# F407.net
KiCad netlist of a schematic drawn in Altium Designer
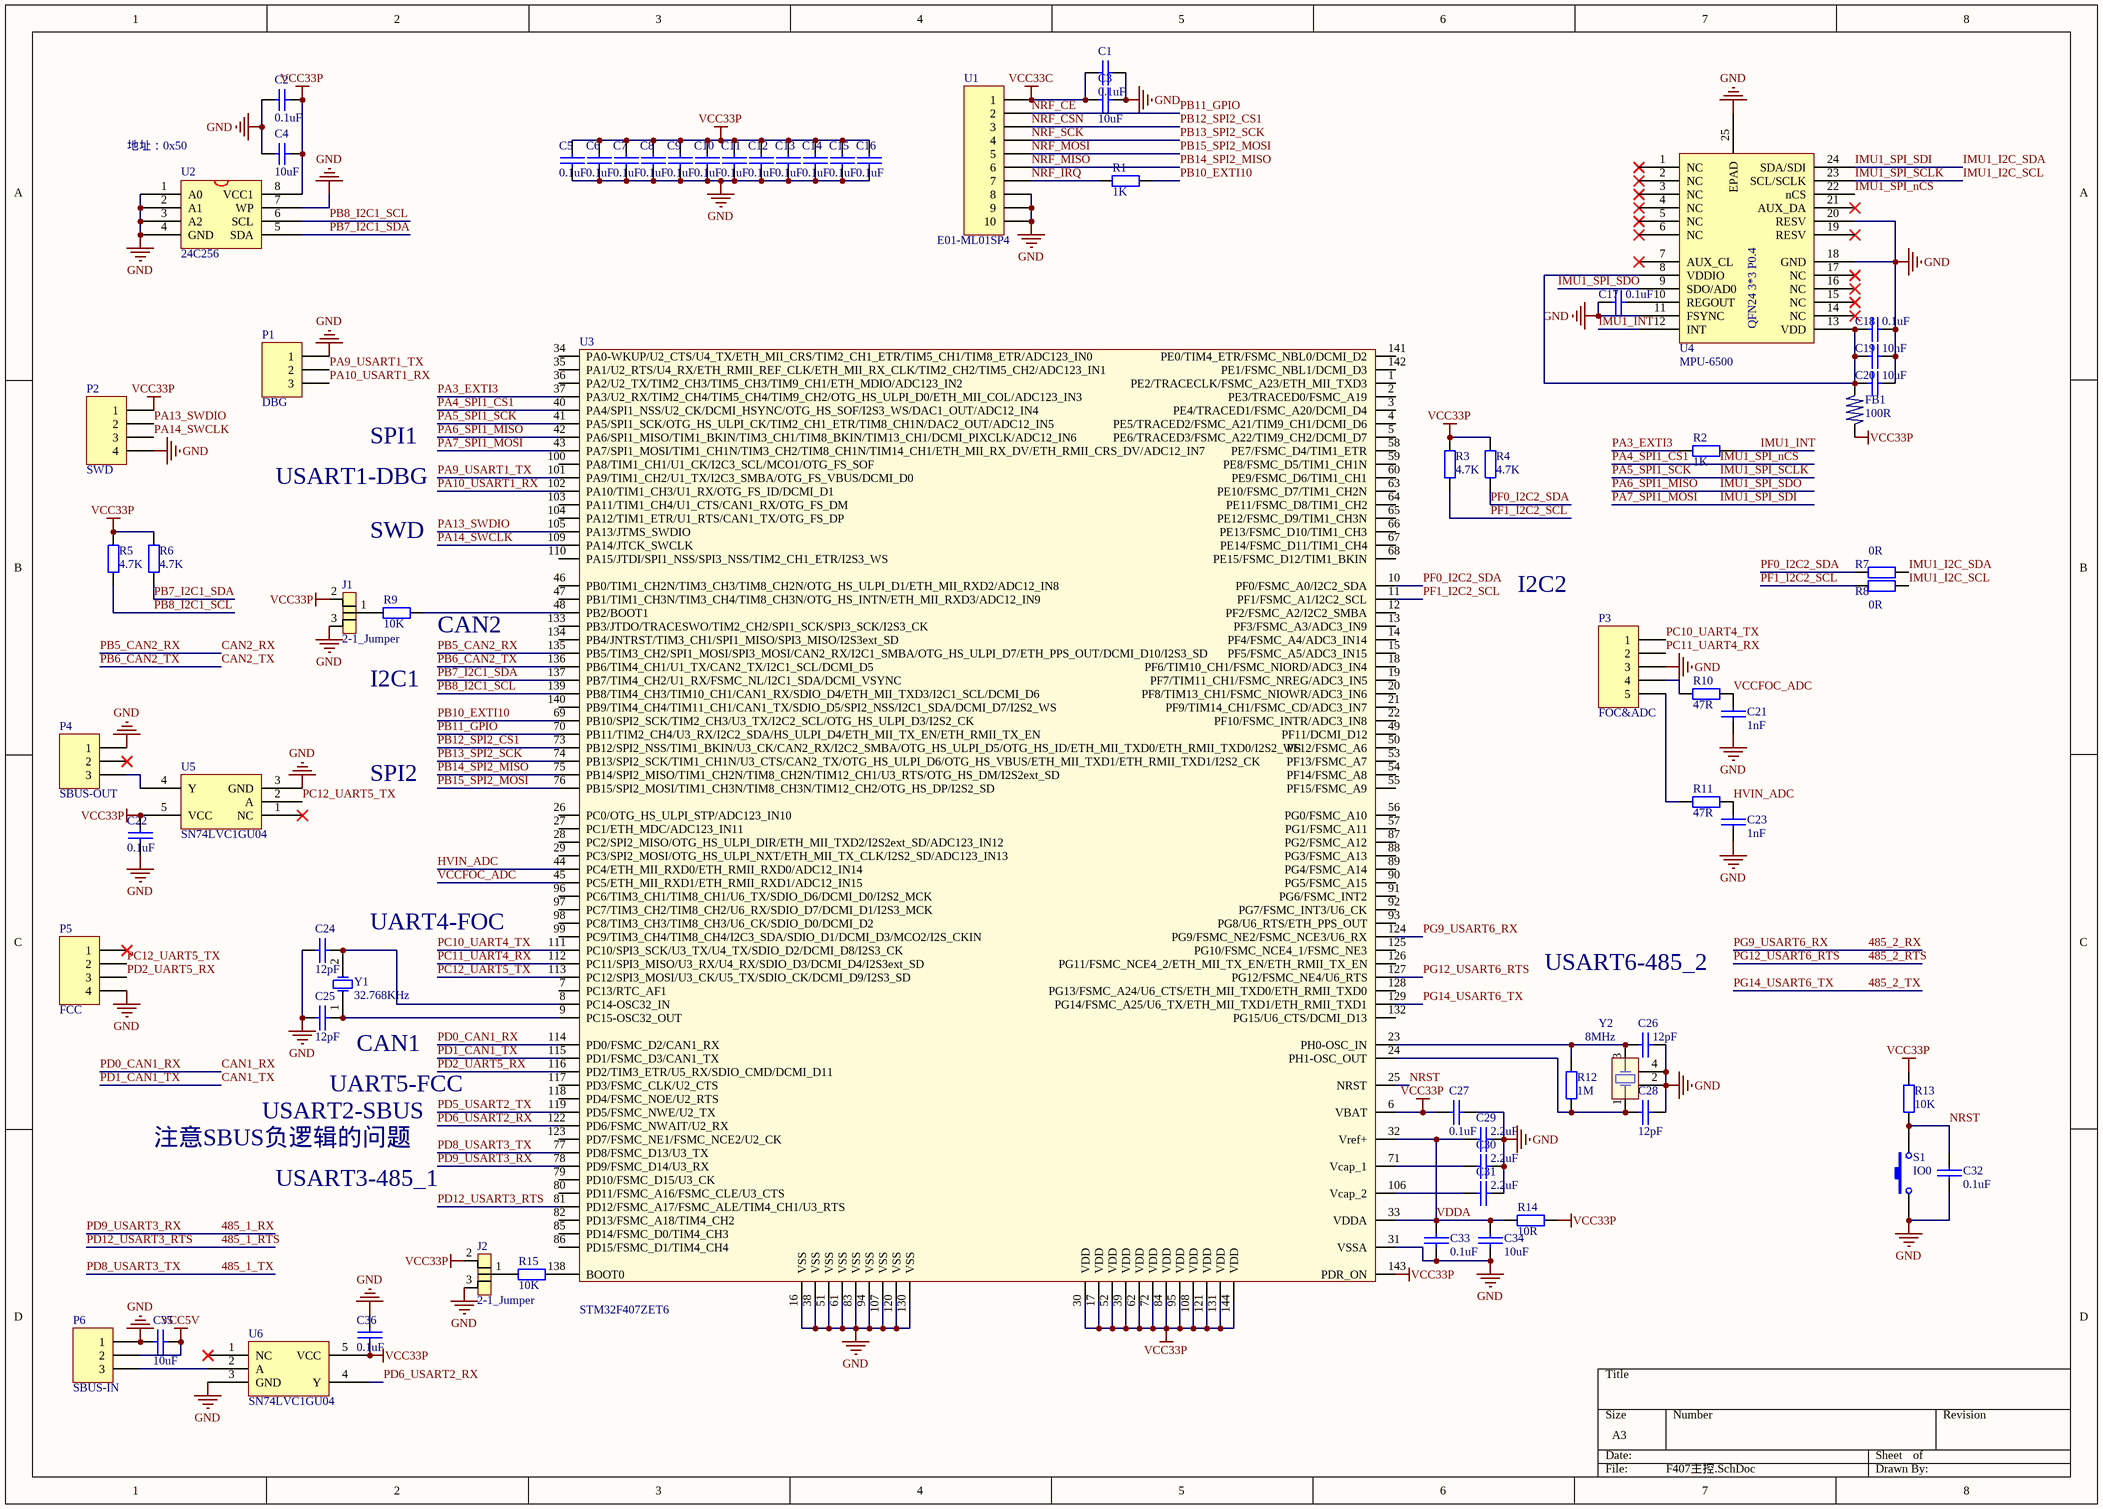
[diagram p0: F407主控.SchDoc]

(export (version "E")
  (design (tool "Eeschema 10.0.6"))
  (components
    (comp (ref "C1")
      (value "0.1uF")
      (footprint "C0805_M")
      (description "Capacitor")
      (libsource (lib "*") (part "CAP"))
    )
    (comp (ref "C2")
      (value "0.1uF")
      (footprint "C0805_M")
      (description "Capacitor")
      (fields (field (name "PUBLISHER") "Altium Limited"))
      (libsource (lib "Miscellaneous Devices") (part "Cap"))
    )
    (comp (ref "C3")
      (value "10uF")
      (footprint "C0805_M")
      (description "Capacitor")
      (libsource (lib "*") (part "CAP"))
    )
    (comp (ref "C4")
      (value "10uF")
      (footprint "C0805_M")
      (description "Capacitor")
      (fields (field (name "PUBLISHER") "Altium Limited"))
      (libsource (lib "Miscellaneous Devices") (part "Cap"))
    )
    (comp (ref "C5")
      (value "0.1uF")
      (footprint "C0805_M")
      (description "Capacitor")
      (libsource (lib "*") (part "CAP"))
    )
    (comp (ref "C6")
      (value "0.1uF")
      (footprint "C0805_M")
      (description "Capacitor")
      (libsource (lib "*") (part "CAP"))
    )
    (comp (ref "C7")
      (value "0.1uF")
      (footprint "C0805_M")
      (description "Capacitor")
      (libsource (lib "*") (part "CAP"))
    )
    (comp (ref "C8")
      (value "0.1uF")
      (footprint "C0805_M")
      (description "Capacitor")
      (libsource (lib "*") (part "CAP"))
    )
    (comp (ref "C9")
      (value "0.1uF")
      (footprint "C0805_M")
      (description "Capacitor")
      (libsource (lib "*") (part "CAP"))
    )
    (comp (ref "C10")
      (value "0.1uF")
      (footprint "C0805_M")
      (description "Capacitor")
      (libsource (lib "*") (part "CAP"))
    )
    (comp (ref "C11")
      (value "0.1uF")
      (footprint "C0805_M")
      (description "Capacitor")
      (libsource (lib "*") (part "CAP"))
    )
    (comp (ref "C12")
      (value "0.1uF")
      (footprint "C0805_M")
      (description "Capacitor")
      (libsource (lib "*") (part "CAP"))
    )
    (comp (ref "C13")
      (value "0.1uF")
      (footprint "C0805_M")
      (description "Capacitor")
      (libsource (lib "*") (part "CAP"))
    )
    (comp (ref "C14")
      (value "0.1uF")
      (footprint "C0805_M")
      (description "Capacitor")
      (libsource (lib "*") (part "CAP"))
    )
    (comp (ref "C15")
      (value "0.1uF")
      (footprint "C0805_M")
      (description "Capacitor")
      (libsource (lib "*") (part "CAP"))
    )
    (comp (ref "C16")
      (value "0.1uF")
      (footprint "C0805_M")
      (description "Capacitor")
      (libsource (lib "*") (part "CAP"))
    )
    (comp (ref "C17")
      (value "0.1uF")
      (footprint "C0805_M")
      (description "Capacitor")
      (libsource (lib "*") (part "CAP"))
    )
    (comp (ref "C18")
      (value "0.1uF")
      (footprint "C0805_M")
      (description "Capacitor")
      (libsource (lib "*") (part "CAP"))
    )
    (comp (ref "C19")
      (value "10nF")
      (footprint "C0805_M")
      (description "Capacitor")
      (libsource (lib "*") (part "CAP"))
    )
    (comp (ref "C20")
      (value "10uF")
      (footprint "C0805_M")
      (description "Capacitor")
      (libsource (lib "*") (part "CAP"))
    )
    (comp (ref "C21")
      (value "1nF")
      (footprint "C0805_M")
      (description "Capacitor")
      (libsource (lib "*") (part "CAP"))
    )
    (comp (ref "C22")
      (value "0.1uF")
      (footprint "C0805_M")
      (description "Capacitor")
      (libsource (lib "*") (part "CAP"))
    )
    (comp (ref "C23")
      (value "1nF")
      (footprint "C0805_M")
      (description "Capacitor")
      (libsource (lib "*") (part "CAP"))
    )
    (comp (ref "C24")
      (value "12pF")
      (footprint "C0805_M")
      (description "Capacitor")
      (libsource (lib "*") (part "CAP"))
    )
    (comp (ref "C25")
      (value "12pF")
      (footprint "C0805_M")
      (description "Capacitor")
      (libsource (lib "*") (part "CAP"))
    )
    (comp (ref "C26")
      (value "12pF")
      (footprint "C0805_M")
      (description "Capacitor")
      (libsource (lib "*") (part "CAP"))
    )
    (comp (ref "C27")
      (value "0.1uF")
      (footprint "C0805_M")
      (description "Capacitor")
      (libsource (lib "*") (part "CAP"))
    )
    (comp (ref "C28")
      (value "12pF")
      (footprint "C0805_M")
      (description "Capacitor")
      (libsource (lib "*") (part "CAP"))
    )
    (comp (ref "C29")
      (value "2.2uF")
      (footprint "C0805_M")
      (description "Capacitor")
      (libsource (lib "*") (part "CAP"))
    )
    (comp (ref "C30")
      (value "2.2uF")
      (footprint "C0805_M")
      (description "Capacitor")
      (libsource (lib "*") (part "CAP"))
    )
    (comp (ref "C31")
      (value "2.2uF")
      (footprint "C0805_M")
      (description "Capacitor")
      (libsource (lib "*") (part "CAP"))
    )
    (comp (ref "C32")
      (value "0.1uF")
      (footprint "C0805_M")
      (description "Capacitor")
      (libsource (lib "*") (part "CAP"))
    )
    (comp (ref "C33")
      (value "0.1uF")
      (footprint "C0805_M")
      (description "Capacitor")
      (libsource (lib "*") (part "CAP"))
    )
    (comp (ref "C34")
      (value "10uF")
      (footprint "C0805_M")
      (description "Capacitor")
      (libsource (lib "*") (part "CAP"))
    )
    (comp (ref "C35")
      (value "10uF")
      (footprint "C0805_M")
      (description "Capacitor")
      (libsource (lib "*") (part "CAP"))
    )
    (comp (ref "C36")
      (value "0.1uF")
      (footprint "C0805_M")
      (description "Capacitor")
      (libsource (lib "*") (part "CAP"))
    )
    (comp (ref "FB1") (value "100R") (footprint "R0805_M") (libsource (lib "EXPLORER") (part "L")))
    (comp (ref "J1")
      (value "2-1_Jumper")
      (footprint "2-1_Jumper")
      (libsource (lib "XL6005") (part "2-1_Jumper"))
    )
    (comp (ref "J2")
      (value "2-1_Jumper")
      (footprint "2-1_Jumper")
      (libsource (lib "XL6005") (part "2-1_Jumper"))
    )
    (comp (ref "P1")
      (value "DBG")
      (footprint "XH2.54-LI-3P")
      (description "Header, 3-Pin")
      (fields (field (name "PUBLISHER") "Altium Limited"))
      (libsource (lib "Miscellaneous Connectors") (part "Header 3"))
    )
    (comp (ref "P2")
      (value "SWD")
      (footprint "XH2.54-LI-4P")
      (description "Header, 4-Pin")
      (fields (field (name "PUBLISHER") "Altium Limited"))
      (libsource (lib "Miscellaneous Connectors") (part "Header 4"))
    )
    (comp (ref "P3")
      (value "FOC&ADC")
      (footprint "XH2.54-LI-5P")
      (description "Header, 5-Pin")
      (fields (field (name "PUBLISHER") "Altium Limited"))
      (libsource (lib "Miscellaneous Connectors") (part "Header 5"))
    )
    (comp (ref "P4")
      (value "SBUS-OUT")
      (footprint "XH2.54-LI-3P")
      (description "Header, 3-Pin")
      (fields (field (name "PUBLISHER") "Altium Limited"))
      (libsource (lib "Miscellaneous Connectors") (part "Header 3"))
    )
    (comp (ref "P5")
      (value "FCC")
      (footprint "XH2.54-LI-4P")
      (description "Header, 4-Pin")
      (fields (field (name "PUBLISHER") "Altium Limited"))
      (libsource (lib "Miscellaneous Connectors") (part "Header 4"))
    )
    (comp (ref "P6")
      (value "SBUS-IN")
      (footprint "XH2.54-LI-3P")
      (description "Header, 3-Pin")
      (fields (field (name "PUBLISHER") "Altium Limited"))
      (libsource (lib "Miscellaneous Connectors") (part "Header 3"))
    )
    (comp (ref "R1")
      (value "1K")
      (footprint "R0805_M")
      (description "Resistor")
      (fields (field (name "PUBLISHER") "Altium Limited"))
      (libsource (lib "") (part "Res2_1"))
    )
    (comp (ref "R2")
      (value "1K")
      (footprint "R0805_M")
      (description "Resistor")
      (fields (field (name "PUBLISHER") "Altium Limited"))
      (libsource (lib "") (part "Res2_1"))
    )
    (comp (ref "R3")
      (value "4.7K")
      (footprint "R0805_M")
      (description "Resistor")
      (fields (field (name "PUBLISHER") "Altium Limited"))
      (libsource (lib "") (part "Res2_2"))
    )
    (comp (ref "R4")
      (value "4.7K")
      (footprint "R0805_M")
      (description "Resistor")
      (fields (field (name "PUBLISHER") "Altium Limited"))
      (libsource (lib "") (part "Res2_2"))
    )
    (comp (ref "R5")
      (value "4.7K")
      (footprint "R0805_M")
      (description "Resistor")
      (fields (field (name "PUBLISHER") "Altium Limited"))
      (libsource (lib "") (part "Res2_2"))
    )
    (comp (ref "R6")
      (value "4.7K")
      (footprint "R0805_M")
      (description "Resistor")
      (fields (field (name "PUBLISHER") "Altium Limited"))
      (libsource (lib "") (part "Res2_2"))
    )
    (comp (ref "R7")
      (value "0R")
      (footprint "R0805_M")
      (description "Resistor")
      (fields (field (name "PUBLISHER") "Altium Limited"))
      (libsource (lib "") (part "Res2_1"))
    )
    (comp (ref "R8")
      (value "0R")
      (footprint "R0805_M")
      (description "Resistor")
      (fields (field (name "PUBLISHER") "Altium Limited"))
      (libsource (lib "") (part "Res2_1"))
    )
    (comp (ref "R9")
      (value "10K")
      (footprint "R0805_M")
      (description "Resistor")
      (fields (field (name "PUBLISHER") "Altium Limited"))
      (libsource (lib "") (part "Res2_1"))
    )
    (comp (ref "R10")
      (value "47R")
      (footprint "R0805_M")
      (description "Resistor")
      (fields (field (name "PUBLISHER") "Altium Limited"))
      (libsource (lib "Miscellaneous Devices") (part "Res2"))
    )
    (comp (ref "R11")
      (value "47R")
      (footprint "R0805_M")
      (description "Resistor")
      (fields (field (name "PUBLISHER") "Altium Limited"))
      (libsource (lib "Miscellaneous Devices") (part "Res2"))
    )
    (comp (ref "R12")
      (value "1M")
      (footprint "R0805_M")
      (description "Resistor")
      (fields (field (name "PUBLISHER") "Altium Limited"))
      (libsource (lib "") (part "Res2_3"))
    )
    (comp (ref "R13")
      (value "10K")
      (footprint "R0805_M")
      (description "Resistor")
      (fields (field (name "PUBLISHER") "Altium Limited"))
      (libsource (lib "") (part "Res2_2"))
    )
    (comp (ref "R14")
      (value "10R")
      (footprint "R0805_M")
      (description "Resistor")
      (fields (field (name "PUBLISHER") "Altium Limited"))
      (libsource (lib "") (part "Res2_1"))
    )
    (comp (ref "R15")
      (value "10K")
      (footprint "R0805_M")
      (description "Resistor")
      (fields (field (name "PUBLISHER") "Altium Limited"))
      (libsource (lib "") (part "Res2_1"))
    )
    (comp (ref "S1")
      (value "IO0")
      (footprint "KEY_M")
      (description "Switch")
      (fields (field (name "PUBLISHER") "Altium Limited"))
      (libsource (lib "Miscellaneous Devices") (part "SW-PB"))
    )
    (comp (ref "U1")
      (value "E01-ML01SP4")
      (footprint "PE01-ML01SP4")
      (description "Header, 10-Pin")
      (fields (field (name "PUBLISHER") "Altium Limited"))
      (libsource (lib "Miscellaneous Connectors") (part "Header 10"))
    )
    (comp (ref "U2")
      (value "24C256")
      (footprint "SOP-8")
      (libsource (lib "Explorer STM32F407封装库") (part "24C256"))
    )
    (comp (ref "U3")
      (value "STM32F407ZET6")
      (footprint "2.12-矩形QFP封装:LQFP144")
      (libsource (lib "EXPLORER") (part "STM32F407ZET6"))
    )
    (comp (ref "U4")
      (value "MPU-6500")
      (footprint "QFN24-L3.0-W3.0-P0.4")
      (description "6 DoF IMU Footprint QFN24 3*3 P0.4")
      (libsource (lib "XL6005") (part "MPU-6500"))
    )
    (comp (ref "U5")
      (value "SN74LVC1GU04")
      (footprint "SOT-23-5")
      (libsource (lib "") (part "SN74LVC1GU04_1"))
    )
    (comp (ref "U6")
      (value "SN74LVC1GU04")
      (footprint "SOT-23-5")
      (libsource (lib "7688A原理图封装") (part "SN74LVC1GU04"))
    )
    (comp (ref "Y1")
      (value "32.768KHz")
      (footprint "OSC-3215-2P")
      (description "CL=12.5pF")
      (fields (field (name "PUBLISHER") "Altium Limited"))
      (libsource (lib "Miscellaneous Devices") (part "XTAL"))
    )
    (comp (ref "Y2")
      (value "8MHz")
      (footprint "1.09-晶振、晶体:OSC-3225-4P")
      (description "CL=12pF")
      (fields (field (name "PUBLISHER") "Altium Limited"))
      (libsource (lib "XL6005") (part "XTAL-4"))
    )
  )
  (nets
    (net (code "1") (name "/485_1_RTS") (class "Default")
      (node (ref "U3") (pin "81") (pinfunction "PD12/FSMC_A17/FSMC_ALE/TIM4_CH1/U3_RTS_81") (pintype "passive"))
    )
    (net (code "2") (name "/485_1_RX") (class "Default")
      (node (ref "U3") (pin "78") (pinfunction "PD9/FSMC_D14/U3_RX_78") (pintype "passive"))
    )
    (net (code "3") (name "/485_1_TX") (class "Default")
      (node (ref "U3") (pin "77") (pinfunction "PD8/FSMC_D13/U3_TX_77") (pintype "passive"))
    )
    (net (code "4") (name "/485_2_RTS") (class "Default")
      (node (ref "U3") (pin "127") (pinfunction "PG12/FSMC_NE4/U6_RTS_127") (pintype "passive"))
    )
    (net (code "5") (name "/485_2_RX") (class "Default")
      (node (ref "U3") (pin "124") (pinfunction "PG9/FSMC_NE2/FSMC_NCE3/U6_RX_124") (pintype "passive"))
    )
    (net (code "6") (name "/485_2_TX") (class "Default")
      (node (ref "U3") (pin "129") (pinfunction "PG14/FSMC_A25/U6_TX/ETH_MII_TXD1/ETH_RMII_TXD1_129") (pintype "passive"))
    )
    (net (code "7") (name "/CAN1_RX") (class "Default")
      (node (ref "U3") (pin "114") (pinfunction "PD0/FSMC_D2/CAN1_RX_114") (pintype "passive"))
    )
    (net (code "8") (name "/CAN1_TX") (class "Default")
      (node (ref "U3") (pin "115") (pinfunction "PD1/FSMC_D3/CAN1_TX_115") (pintype "passive"))
    )
    (net (code "9") (name "/CAN2_RX") (class "Default")
      (node (ref "U3") (pin "135") (pinfunction "PB5/TIM3_CH2/SPI1_MOSI/SPI3_MOSI/CAN2_RX/I2C1_SMBA/OTG_HS_ULPI_D7/ETH_PPS_OUT/DCMI_D10/I2S3_SD_135") (pintype "passive"))
    )
    (net (code "10") (name "/CAN2_TX") (class "Default")
      (node (ref "U3") (pin "136") (pinfunction "PB6/TIM4_CH1/U1_TX/CAN2_TX/I2C1_SCL/DCMI_D5_136") (pintype "passive"))
    )
    (net (code "11") (name "/HVIN_ADC") (class "Default")
      (node (ref "C23") (pin "2") (pinfunction "2_2") (pintype "passive"))
      (node (ref "R11") (pin "2") (pinfunction "2_2") (pintype "passive"))
      (node (ref "U3") (pin "44") (pinfunction "PC4/ETH_MII_RXD0/ETH_RMII_RXD0/ADC12_IN14_44") (pintype "passive"))
    )
    (net (code "12") (name "/IMU1_I2C_SCL") (class "Default")
      (node (ref "R8") (pin "1") (pinfunction "1_1") (pintype "passive"))
      (node (ref "U3") (pin "41") (pinfunction "PA5/SPI1_SCK/OTG_HS_ULPI_CK/TIM2_CH1_ETR/TIM8_CH1N/DAC2_OUT/ADC12_IN5_41") (pintype "passive"))
      (node (ref "U4") (pin "23") (pinfunction "SCL/SCLK_23") (pintype "passive"))
    )
    (net (code "13") (name "/IMU1_I2C_SDA") (class "Default")
      (node (ref "R7") (pin "1") (pinfunction "1_1") (pintype "passive"))
      (node (ref "U3") (pin "43") (pinfunction "PA7/SPI1_MOSI/TIM1_CH1N/TIM3_CH2/TIM8_CH1N/TIM14_CH1/ETH_MII_RX_DV/ETH_RMII_CRS_DV/ADC12_IN7_43") (pintype "passive"))
      (node (ref "U4") (pin "24") (pinfunction "SDA/SDI_24") (pintype "passive"))
    )
    (net (code "14") (name "/IMU1_INT") (class "Default")
      (node (ref "R2") (pin "1") (pinfunction "1_1") (pintype "passive"))
      (node (ref "U4") (pin "12") (pinfunction "INT_12") (pintype "passive"))
    )
    (net (code "15") (name "/IMU1_SPI_SDO") (class "Default")
      (node (ref "U3") (pin "42") (pinfunction "PA6/SPI1_MISO/TIM1_BKIN/TIM3_CH1/TIM8_BKIN/TIM13_CH1/DCMI_PIXCLK/ADC12_IN6_42") (pintype "passive"))
      (node (ref "U4") (pin "9") (pinfunction "SDO/AD0_9") (pintype "passive"))
    )
    (net (code "16") (name "/IMU1_SPI_nCS") (class "Default")
      (node (ref "U3") (pin "40") (pinfunction "PA4/SPI1_NSS/U2_CK/DCMI_HSYNC/OTG_HS_SOF/I2S3_WS/DAC1_OUT/ADC12_IN4_40") (pintype "passive"))
      (node (ref "U4") (pin "22") (pinfunction "nCS_22") (pintype "passive"))
    )
    (net (code "17") (name "/NRF_CE") (class "Default")
      (node (ref "U1") (pin "2") (pinfunction "2_2") (pintype "passive"))
      (node (ref "U3") (pin "70") (pinfunction "PB11/TIM2_CH4/U3_RX/I2C2_SDA/HS_ULPI_D4/ETH_MII_TX_EN/ETH_RMII_TX_EN_70") (pintype "passive"))
    )
    (net (code "18") (name "/NRF_CSN") (class "Default")
      (node (ref "U1") (pin "3") (pinfunction "3_3") (pintype "passive"))
      (node (ref "U3") (pin "73") (pinfunction "PB12/SPI2_NSS/TIM1_BKIN/U3_CK/CAN2_RX/I2C2_SMBA/OTG_HS_ULPI_D5/OTG_HS_ID/ETH_MII_TXD0/ETH_RMII_TXD0/I2S2_WS_73") (pintype "passive"))
    )
    (net (code "19") (name "/NRF_IRQ") (class "Default")
      (node (ref "R1") (pin "2") (pinfunction "2_2") (pintype "passive"))
      (node (ref "U1") (pin "7") (pinfunction "7_7") (pintype "passive"))
    )
    (net (code "20") (name "/NRF_MISO") (class "Default")
      (node (ref "U1") (pin "6") (pinfunction "6_6") (pintype "passive"))
      (node (ref "U3") (pin "75") (pinfunction "PB14/SPI2_MISO/TIM1_CH2N/TIM8_CH2N/TIM12_CH1/U3_RTS/OTG_HS_DM/I2S2ext_SD_75") (pintype "passive"))
    )
    (net (code "21") (name "/NRF_MOSI") (class "Default")
      (node (ref "U1") (pin "5") (pinfunction "5_5") (pintype "passive"))
      (node (ref "U3") (pin "76") (pinfunction "PB15/SPI2_MOSI/TIM1_CH3N/TIM8_CH3N/TIM12_CH2/OTG_HS_DP/I2S2_SD_76") (pintype "passive"))
    )
    (net (code "22") (name "/NRF_SCK") (class "Default")
      (node (ref "U1") (pin "4") (pinfunction "4_4") (pintype "passive"))
      (node (ref "U3") (pin "74") (pinfunction "PB13/SPI2_SCK/TIM1_CH1N/U3_CTS/CAN2_TX/OTG_HS_ULPI_D6/OTG_HS_VBUS/ETH_MII_TXD1/ETH_RMII_TXD1/I2S2_CK_74") (pintype "passive"))
    )
    (net (code "23") (name "/NRST") (class "Default")
      (node (ref "C32") (pin "2") (pinfunction "2_2") (pintype "passive"))
      (node (ref "R13") (pin "2") (pinfunction "2_2") (pintype "passive"))
      (node (ref "S1") (pin "2") (pinfunction "2_2") (pintype "passive"))
      (node (ref "U3") (pin "25") (pinfunction "NRST_25") (pintype "passive"))
    )
    (net (code "24") (name "/PA3_EXTI3") (class "Default")
      (node (ref "R2") (pin "2") (pinfunction "2_2") (pintype "passive"))
      (node (ref "U3") (pin "37") (pinfunction "PA3/U2_RX/TIM2_CH4/TIM5_CH4/TIM9_CH2/OTG_HS_ULPI_D0/ETH_MII_COL/ADC123_IN3_37") (pintype "passive"))
    )
    (net (code "25") (name "/PA9_USART1_TX") (class "Default")
      (node (ref "P1") (pin "2") (pinfunction "2_2") (pintype "passive"))
      (node (ref "U3") (pin "101") (pinfunction "PA9/TIM1_CH2/U1_TX/I2C3_SMBA/OTG_FS_VBUS/DCMI_D0_101") (pintype "passive"))
    )
    (net (code "26") (name "/PA10_USART1_RX") (class "Default")
      (node (ref "P1") (pin "3") (pinfunction "3_3") (pintype "passive"))
      (node (ref "U3") (pin "102") (pinfunction "PA10/TIM1_CH3/U1_RX/OTG_FS_ID/DCMI_D1_102") (pintype "passive"))
    )
    (net (code "27") (name "/PA13_SWDIO") (class "Default")
      (node (ref "P2") (pin "2") (pinfunction "2_2") (pintype "passive"))
      (node (ref "U3") (pin "105") (pinfunction "PA13/JTMS_SWDIO_105") (pintype "passive"))
    )
    (net (code "28") (name "/PA14_SWCLK") (class "Default")
      (node (ref "P2") (pin "3") (pinfunction "3_3") (pintype "passive"))
      (node (ref "U3") (pin "109") (pinfunction "PA14/JTCK_SWCLK_109") (pintype "passive"))
    )
    (net (code "29") (name "/PB7_I2C1_SDA") (class "Default")
      (node (ref "R6") (pin "2") (pinfunction "2_2") (pintype "passive"))
      (node (ref "U2") (pin "5") (pinfunction "SDA_5") (pintype "passive"))
      (node (ref "U3") (pin "137") (pinfunction "PB7/TIM4_CH2/U1_RX/FSMC_NL/I2C1_SDA/DCMI_VSYNC_137") (pintype "passive"))
    )
    (net (code "30") (name "/PB8_I2C1_SCL") (class "Default")
      (node (ref "R5") (pin "2") (pinfunction "2_2") (pintype "passive"))
      (node (ref "U2") (pin "6") (pinfunction "SCL_6") (pintype "passive"))
      (node (ref "U3") (pin "139") (pinfunction "PB8/TIM4_CH3/TIM10_CH1/CAN1_RX/SDIO_D4/ETH_MII_TXD3/I2C1_SCL/DCMI_D6_139") (pintype "passive"))
    )
    (net (code "31") (name "/PB10_EXTI10") (class "Default")
      (node (ref "R1") (pin "1") (pinfunction "1_1") (pintype "passive"))
      (node (ref "U3") (pin "69") (pinfunction "PB10/SPI2_SCK/TIM2_CH3/U3_TX/I2C2_SCL/OTG_HS_ULPI_D3/I2S2_CK_69") (pintype "passive"))
    )
    (net (code "32") (name "/PC10_UART4_TX") (class "Default")
      (node (ref "P3") (pin "1") (pinfunction "1_1") (pintype "passive"))
      (node (ref "U3") (pin "111") (pinfunction "PC10/SPI3_SCK/U3_TX/U4_TX/SDIO_D2/DCMI_D8/I2S3_CK_111") (pintype "passive"))
    )
    (net (code "33") (name "/PC11_UART4_RX") (class "Default")
      (node (ref "P3") (pin "2") (pinfunction "2_2") (pintype "passive"))
      (node (ref "U3") (pin "112") (pinfunction "PC11/SPI3_MISO/U3_RX/U4_RX/SDIO_D3/DCMI_D4/I2S3ext_SD_112") (pintype "passive"))
    )
    (net (code "34") (name "/PC12_UART5_TX") (class "Default")
      (node (ref "P5") (pin "2") (pinfunction "2_2") (pintype "passive"))
      (node (ref "U3") (pin "113") (pinfunction "PC12/SPI3_MOSI/U3_CK/U5_TX/SDIO_CK/DCMI_D9/I2S3_SD_113") (pintype "passive"))
      (node (ref "U5") (pin "2") (pinfunction "A_2") (pintype "passive"))
    )
    (net (code "35") (name "/PD2_UART5_RX") (class "Default")
      (node (ref "P5") (pin "3") (pinfunction "3_3") (pintype "passive"))
      (node (ref "U3") (pin "116") (pinfunction "PD2/TIM3_ETR/U5_RX/SDIO_CMD/DCMI_D11_116") (pintype "passive"))
    )
    (net (code "36") (name "/PD5_USART2_TX") (class "Default")
      (node (ref "U3") (pin "119") (pinfunction "PD5/FSMC_NWE/U2_TX_119") (pintype "passive"))
    )
    (net (code "37") (name "/PD6_USART2_RX") (class "Default")
      (node (ref "U3") (pin "122") (pinfunction "PD6/FSMC_NWAIT/U2_RX_122") (pintype "passive"))
      (node (ref "U6") (pin "4") (pinfunction "Y_4") (pintype "passive"))
    )
    (net (code "38") (name "/PF0_I2C2_SDA") (class "Default")
      (node (ref "R4") (pin "2") (pinfunction "2_2") (pintype "passive"))
      (node (ref "R7") (pin "2") (pinfunction "2_2") (pintype "passive"))
      (node (ref "U3") (pin "10") (pinfunction "PF0/FSMC_A0/I2C2_SDA_10") (pintype "passive"))
    )
    (net (code "39") (name "/PF1_I2C2_SCL") (class "Default")
      (node (ref "R3") (pin "2") (pinfunction "2_2") (pintype "passive"))
      (node (ref "R8") (pin "2") (pinfunction "2_2") (pintype "passive"))
      (node (ref "U3") (pin "11") (pinfunction "PF1/FSMC_A1/I2C2_SCL_11") (pintype "passive"))
    )
    (net (code "40") (name "/VCCFOC_ADC") (class "Default")
      (node (ref "C21") (pin "2") (pinfunction "2_2") (pintype "passive"))
      (node (ref "R10") (pin "2") (pinfunction "2_2") (pintype "passive"))
      (node (ref "U3") (pin "45") (pinfunction "PC5/ETH_MII_RXD1/ETH_RMII_RXD1/ADC12_IN15_45") (pintype "passive"))
    )
    (net (code "41") (name "/VDDA") (class "Default")
      (node (ref "C29") (pin "1") (pinfunction "1_1") (pintype "passive"))
      (node (ref "C33") (pin "2") (pinfunction "2_2") (pintype "passive"))
      (node (ref "C34") (pin "2") (pinfunction "2_2") (pintype "passive"))
      (node (ref "R14") (pin "2") (pinfunction "2_2") (pintype "passive"))
      (node (ref "U3") (pin "32") (pinfunction "Vref+_32") (pintype "passive"))
      (node (ref "U3") (pin "33") (pinfunction "VDDA_33") (pintype "passive"))
    )
    (net (code "42") (name "GND") (class "Default")
      (node (ref "C1") (pin "1") (pinfunction "1_1") (pintype "passive"))
      (node (ref "C10") (pin "1") (pinfunction "1_1") (pintype "passive"))
      (node (ref "C11") (pin "1") (pinfunction "1_1") (pintype "passive"))
      (node (ref "C12") (pin "1") (pinfunction "1_1") (pintype "passive"))
      (node (ref "C13") (pin "1") (pinfunction "1_1") (pintype "passive"))
      (node (ref "C14") (pin "1") (pinfunction "1_1") (pintype "passive"))
      (node (ref "C15") (pin "1") (pinfunction "1_1") (pintype "passive"))
      (node (ref "C16") (pin "1") (pinfunction "1_1") (pintype "passive"))
      (node (ref "C17") (pin "2") (pinfunction "2_2") (pintype "passive"))
      (node (ref "C18") (pin "1") (pinfunction "1_1") (pintype "passive"))
      (node (ref "C19") (pin "1") (pinfunction "1_1") (pintype "passive"))
      (node (ref "C2") (pin "1") (pinfunction "1_1") (pintype "passive"))
      (node (ref "C20") (pin "1") (pinfunction "1_1") (pintype "passive"))
      (node (ref "C21") (pin "1") (pinfunction "1_1") (pintype "passive"))
      (node (ref "C22") (pin "1") (pinfunction "1_1") (pintype "passive"))
      (node (ref "C23") (pin "1") (pinfunction "1_1") (pintype "passive"))
      (node (ref "C24") (pin "1") (pinfunction "1_1") (pintype "passive"))
      (node (ref "C25") (pin "1") (pinfunction "1_1") (pintype "passive"))
      (node (ref "C26") (pin "2") (pinfunction "2_2") (pintype "passive"))
      (node (ref "C27") (pin "1") (pinfunction "1_1") (pintype "passive"))
      (node (ref "C28") (pin "2") (pinfunction "2_2") (pintype "passive"))
      (node (ref "C29") (pin "2") (pinfunction "2_2") (pintype "passive"))
      (node (ref "C3") (pin "1") (pinfunction "1_1") (pintype "passive"))
      (node (ref "C30") (pin "2") (pinfunction "2_2") (pintype "passive"))
      (node (ref "C31") (pin "2") (pinfunction "2_2") (pintype "passive"))
      (node (ref "C32") (pin "1") (pinfunction "1_1") (pintype "passive"))
      (node (ref "C33") (pin "1") (pinfunction "1_1") (pintype "passive"))
      (node (ref "C34") (pin "1") (pinfunction "1_1") (pintype "passive"))
      (node (ref "C35") (pin "2") (pinfunction "2_2") (pintype "passive"))
      (node (ref "C36") (pin "2") (pinfunction "2_2") (pintype "passive"))
      (node (ref "C4") (pin "1") (pinfunction "1_1") (pintype "passive"))
      (node (ref "C5") (pin "1") (pinfunction "1_1") (pintype "passive"))
      (node (ref "C6") (pin "1") (pinfunction "1_1") (pintype "passive"))
      (node (ref "C7") (pin "1") (pinfunction "1_1") (pintype "passive"))
      (node (ref "C8") (pin "1") (pinfunction "1_1") (pintype "passive"))
      (node (ref "C9") (pin "1") (pinfunction "1_1") (pintype "passive"))
      (node (ref "J1") (pin "3") (pintype "passive"))
      (node (ref "J2") (pin "3") (pintype "passive"))
      (node (ref "P1") (pin "1") (pinfunction "1_1") (pintype "passive"))
      (node (ref "P2") (pin "4") (pinfunction "4_4") (pintype "passive"))
      (node (ref "P3") (pin "3") (pinfunction "3_3") (pintype "passive"))
      (node (ref "P4") (pin "1") (pinfunction "1_1") (pintype "passive"))
      (node (ref "P5") (pin "4") (pinfunction "4_4") (pintype "passive"))
      (node (ref "P6") (pin "1") (pinfunction "1_1") (pintype "passive"))
      (node (ref "S1") (pin "1") (pinfunction "1_1") (pintype "passive"))
      (node (ref "U1") (pin "10") (pinfunction "10_10") (pintype "passive"))
      (node (ref "U1") (pin "8") (pinfunction "8_8") (pintype "passive"))
      (node (ref "U1") (pin "9") (pinfunction "9_9") (pintype "passive"))
      (node (ref "U2") (pin "1") (pinfunction "A0_1") (pintype "passive"))
      (node (ref "U2") (pin "2") (pinfunction "A1_2") (pintype "passive"))
      (node (ref "U2") (pin "3") (pinfunction "A2_3") (pintype "passive"))
      (node (ref "U2") (pin "4") (pinfunction "GND_4") (pintype "passive"))
      (node (ref "U2") (pin "7") (pinfunction "WP_7") (pintype "passive"))
      (node (ref "U3") (pin "107") (pinfunction "VSS_107") (pintype "passive"))
      (node (ref "U3") (pin "120") (pinfunction "VSS_120") (pintype "passive"))
      (node (ref "U3") (pin "130") (pinfunction "VSS_130") (pintype "passive"))
      (node (ref "U3") (pin "16") (pinfunction "VSS_16") (pintype "passive"))
      (node (ref "U3") (pin "31") (pinfunction "VSSA_31") (pintype "passive"))
      (node (ref "U3") (pin "38") (pinfunction "VSS_38") (pintype "passive"))
      (node (ref "U3") (pin "51") (pinfunction "VSS_51") (pintype "passive"))
      (node (ref "U3") (pin "61") (pinfunction "VSS_61") (pintype "passive"))
      (node (ref "U3") (pin "83") (pinfunction "VSS_83") (pintype "passive"))
      (node (ref "U3") (pin "94") (pinfunction "VSS_94") (pintype "passive"))
      (node (ref "U4") (pin "11") (pinfunction "FSYNC_11") (pintype "passive"))
      (node (ref "U4") (pin "18") (pinfunction "GND_18") (pintype "passive"))
      (node (ref "U4") (pin "20") (pinfunction "RESV_20") (pintype "passive"))
      (node (ref "U4") (pin "25") (pinfunction "EPAD_25") (pintype "passive"))
      (node (ref "U5") (pin "3") (pinfunction "GND_3") (pintype "passive"))
      (node (ref "U6") (pin "3") (pinfunction "GND_3") (pintype "passive"))
      (node (ref "Y2") (pin "2") (pinfunction "GND_2") (pintype "passive"))
      (node (ref "Y2") (pin "4") (pinfunction "GND_4") (pintype "passive"))
    )
    (net (code "43") (name "Net-(J1-Pad1)") (class "Default")
      (node (ref "J1") (pin "1") (pintype "passive"))
      (node (ref "R9") (pin "2") (pinfunction "2_2") (pintype "passive"))
    )
    (net (code "44") (name "Net-(J2-Pad1)") (class "Default")
      (node (ref "J2") (pin "1") (pintype "passive"))
      (node (ref "R15") (pin "2") (pinfunction "2_2") (pintype "passive"))
    )
    (net (code "45") (name "Net-(P3-Pad4)") (class "Default")
      (node (ref "P3") (pin "4") (pinfunction "4_4") (pintype "passive"))
      (node (ref "R10") (pin "1") (pinfunction "1_1") (pintype "passive"))
    )
    (net (code "46") (name "Net-(P3-Pad5)") (class "Default")
      (node (ref "P3") (pin "5") (pinfunction "5_5") (pintype "passive"))
      (node (ref "R11") (pin "1") (pinfunction "1_1") (pintype "passive"))
    )
    (net (code "47") (name "Net-(U3-BOOT0)") (class "Default")
      (node (ref "R15") (pin "1") (pinfunction "1_1") (pintype "passive"))
      (node (ref "U3") (pin "138") (pinfunction "BOOT0_138") (pintype "passive"))
    )
    (net (code "48") (name "Net-(U3-PB2{slash}BOOT1)") (class "Default")
      (node (ref "R9") (pin "1") (pinfunction "1_1") (pintype "passive"))
      (node (ref "U3") (pin "48") (pinfunction "PB2/BOOT1_48") (pintype "passive"))
    )
    (net (code "49") (name "Net-(U3-PC14-OSC32_IN)") (class "Default")
      (node (ref "C24") (pin "2") (pinfunction "2_2") (pintype "passive"))
      (node (ref "U3") (pin "8") (pinfunction "PC14-OSC32_IN_8") (pintype "passive"))
      (node (ref "Y1") (pin "2") (pinfunction "OSC2_2") (pintype "passive"))
    )
    (net (code "50") (name "Net-(U3-PC15-OSC32_OUT)") (class "Default")
      (node (ref "C25") (pin "2") (pinfunction "2_2") (pintype "passive"))
      (node (ref "U3") (pin "9") (pinfunction "PC15-OSC32_OUT_9") (pintype "passive"))
      (node (ref "Y1") (pin "1") (pinfunction "OSC1_1") (pintype "passive"))
    )
    (net (code "51") (name "Net-(U3-PH0-OSC_IN)") (class "Default")
      (node (ref "C26") (pin "1") (pinfunction "1_1") (pintype "passive"))
      (node (ref "R12") (pin "2") (pinfunction "2_2") (pintype "passive"))
      (node (ref "U3") (pin "23") (pinfunction "PH0-OSC_IN_23") (pintype "passive"))
      (node (ref "Y2") (pin "3") (pinfunction "OSC2_3") (pintype "passive"))
    )
    (net (code "52") (name "Net-(U3-PH1-OSC_OUT)") (class "Default")
      (node (ref "C28") (pin "1") (pinfunction "1_1") (pintype "passive"))
      (node (ref "R12") (pin "1") (pinfunction "1_1") (pintype "passive"))
      (node (ref "U3") (pin "24") (pinfunction "PH1-OSC_OUT_24") (pintype "passive"))
      (node (ref "Y2") (pin "1") (pinfunction "OSC1_1") (pintype "passive"))
    )
    (net (code "53") (name "Net-(U3-Vcap_1)") (class "Default")
      (node (ref "C30") (pin "1") (pinfunction "1_1") (pintype "passive"))
      (node (ref "U3") (pin "71") (pinfunction "Vcap_1_71") (pintype "passive"))
    )
    (net (code "54") (name "Net-(U3-Vcap_2)") (class "Default")
      (node (ref "C31") (pin "1") (pinfunction "1_1") (pintype "passive"))
      (node (ref "U3") (pin "106") (pinfunction "Vcap_2_106") (pintype "passive"))
    )
    (net (code "55") (name "Net-(U4-REGOUT)") (class "Default")
      (node (ref "C17") (pin "1") (pinfunction "1_1") (pintype "passive"))
      (node (ref "U4") (pin "10") (pinfunction "REGOUT_10") (pintype "passive"))
    )
    (net (code "56") (name "Net-(U4-VDD)") (class "Default")
      (node (ref "C18") (pin "2") (pinfunction "2_2") (pintype "passive"))
      (node (ref "C19") (pin "2") (pinfunction "2_2") (pintype "passive"))
      (node (ref "C20") (pin "2") (pinfunction "2_2") (pintype "passive"))
      (node (ref "FB1") (pin "1") (pintype "passive"))
      (node (ref "U4") (pin "13") (pinfunction "VDD_13") (pintype "passive"))
      (node (ref "U4") (pin "8") (pinfunction "VDDIO_8") (pintype "passive"))
    )
    (net (code "57") (name "Net-(U5-Y)") (class "Default")
      (node (ref "P4") (pin "3") (pinfunction "3_3") (pintype "passive"))
      (node (ref "U5") (pin "4") (pinfunction "Y_4") (pintype "passive"))
    )
    (net (code "58") (name "Net-(U6-A)") (class "Default")
      (node (ref "P6") (pin "3") (pinfunction "3_3") (pintype "passive"))
      (node (ref "U6") (pin "2") (pinfunction "A_2") (pintype "passive"))
    )
    (net (code "59") (name "VCC5V") (class "Default")
      (node (ref "C35") (pin "1") (pinfunction "1_1") (pintype "passive"))
      (node (ref "P6") (pin "2") (pinfunction "2_2") (pintype "passive"))
    )
    (net (code "60") (name "VCC33C") (class "Default")
      (node (ref "C1") (pin "2") (pinfunction "2_2") (pintype "passive"))
      (node (ref "C3") (pin "2") (pinfunction "2_2") (pintype "passive"))
      (node (ref "U1") (pin "1") (pinfunction "1_1") (pintype "passive"))
    )
    (net (code "61") (name "VCC33P") (class "Default")
      (node (ref "C10") (pin "2") (pinfunction "2_2") (pintype "passive"))
      (node (ref "C11") (pin "2") (pinfunction "2_2") (pintype "passive"))
      (node (ref "C12") (pin "2") (pinfunction "2_2") (pintype "passive"))
      (node (ref "C13") (pin "2") (pinfunction "2_2") (pintype "passive"))
      (node (ref "C14") (pin "2") (pinfunction "2_2") (pintype "passive"))
      (node (ref "C15") (pin "2") (pinfunction "2_2") (pintype "passive"))
      (node (ref "C16") (pin "2") (pinfunction "2_2") (pintype "passive"))
      (node (ref "C2") (pin "2") (pinfunction "2_2") (pintype "passive"))
      (node (ref "C22") (pin "2") (pinfunction "2_2") (pintype "passive"))
      (node (ref "C27") (pin "2") (pinfunction "2_2") (pintype "passive"))
      (node (ref "C36") (pin "1") (pinfunction "1_1") (pintype "passive"))
      (node (ref "C4") (pin "2") (pinfunction "2_2") (pintype "passive"))
      (node (ref "C5") (pin "2") (pinfunction "2_2") (pintype "passive"))
      (node (ref "C6") (pin "2") (pinfunction "2_2") (pintype "passive"))
      (node (ref "C7") (pin "2") (pinfunction "2_2") (pintype "passive"))
      (node (ref "C8") (pin "2") (pinfunction "2_2") (pintype "passive"))
      (node (ref "C9") (pin "2") (pinfunction "2_2") (pintype "passive"))
      (node (ref "FB1") (pin "2") (pintype "passive"))
      (node (ref "J1") (pin "2") (pintype "passive"))
      (node (ref "J2") (pin "2") (pintype "passive"))
      (node (ref "P2") (pin "1") (pinfunction "1_1") (pintype "passive"))
      (node (ref "R13") (pin "1") (pinfunction "1_1") (pintype "passive"))
      (node (ref "R14") (pin "1") (pinfunction "1_1") (pintype "passive"))
      (node (ref "R3") (pin "1") (pinfunction "1_1") (pintype "passive"))
      (node (ref "R4") (pin "1") (pinfunction "1_1") (pintype "passive"))
      (node (ref "R5") (pin "1") (pinfunction "1_1") (pintype "passive"))
      (node (ref "R6") (pin "1") (pinfunction "1_1") (pintype "passive"))
      (node (ref "U2") (pin "8") (pinfunction "VCC1_8") (pintype "passive"))
      (node (ref "U3") (pin "108") (pinfunction "VDD_108") (pintype "passive"))
      (node (ref "U3") (pin "121") (pinfunction "VDD_121") (pintype "passive"))
      (node (ref "U3") (pin "131") (pinfunction "VDD_131") (pintype "passive"))
      (node (ref "U3") (pin "143") (pinfunction "PDR_ON_143") (pintype "passive"))
      (node (ref "U3") (pin "144") (pinfunction "VDD_144") (pintype "passive"))
      (node (ref "U3") (pin "17") (pinfunction "VDD_17") (pintype "passive"))
      (node (ref "U3") (pin "30") (pinfunction "VDD_30") (pintype "passive"))
      (node (ref "U3") (pin "39") (pinfunction "VDD_39") (pintype "passive"))
      (node (ref "U3") (pin "52") (pinfunction "VDD_52") (pintype "passive"))
      (node (ref "U3") (pin "6") (pinfunction "VBAT_6") (pintype "passive"))
      (node (ref "U3") (pin "62") (pinfunction "VDD_62") (pintype "passive"))
      (node (ref "U3") (pin "72") (pinfunction "VDD_72") (pintype "passive"))
      (node (ref "U3") (pin "84") (pinfunction "VDD_84") (pintype "passive"))
      (node (ref "U3") (pin "95") (pinfunction "VDD_95") (pintype "passive"))
      (node (ref "U5") (pin "5") (pinfunction "VCC_5") (pintype "passive"))
      (node (ref "U6") (pin "5") (pinfunction "VCC_5") (pintype "passive"))
    )
    (net (code "62") (name "unconnected-(P4-Pad2)") (class "Default")
      (node (ref "P4") (pin "2") (pinfunction "2_2") (pintype "passive+no_connect"))
    )
    (net (code "63") (name "unconnected-(P5-Pad1)") (class "Default")
      (node (ref "P5") (pin "1") (pinfunction "1_1") (pintype "passive+no_connect"))
    )
    (net (code "64") (name "unconnected-(U3-PA0-WKUP{slash}U2_CTS{slash}U4_TX{slash}ETH_MII_CRS{slash}TIM2_CH1_ETR{slash}TIM5_CH1{slash}TIM8_ETR{slash}ADC123_IN0-Pad34)") (class "Default")
      (node (ref "U3") (pin "34") (pinfunction "PA0-WKUP/U2_CTS/U4_TX/ETH_MII_CRS/TIM2_CH1_ETR/TIM5_CH1/TIM8_ETR/ADC123_IN0_34") (pintype "passive"))
    )
    (net (code "65") (name "unconnected-(U3-PA1{slash}U2_RTS{slash}U4_RX{slash}ETH_RMII_REF_CLK{slash}ETH_MII_RX_CLK{slash}TIM2_CH2{slash}TIM5_CH2{slash}ADC123_IN1-Pad35)") (class "Default")
      (node (ref "U3") (pin "35") (pinfunction "PA1/U2_RTS/U4_RX/ETH_RMII_REF_CLK/ETH_MII_RX_CLK/TIM2_CH2/TIM5_CH2/ADC123_IN1_35") (pintype "passive"))
    )
    (net (code "66") (name "unconnected-(U3-PA2{slash}U2_TX{slash}TIM2_CH3{slash}TIM5_CH3{slash}TIM9_CH1{slash}ETH_MDIO{slash}ADC123_IN2-Pad36)") (class "Default")
      (node (ref "U3") (pin "36") (pinfunction "PA2/U2_TX/TIM2_CH3/TIM5_CH3/TIM9_CH1/ETH_MDIO/ADC123_IN2_36") (pintype "passive"))
    )
    (net (code "67") (name "unconnected-(U3-PA8{slash}TIM1_CH1{slash}U1_CK{slash}I2C3_SCL{slash}MCO1{slash}OTG_FS_SOF-Pad100)") (class "Default")
      (node (ref "U3") (pin "100") (pinfunction "PA8/TIM1_CH1/U1_CK/I2C3_SCL/MCO1/OTG_FS_SOF_100") (pintype "passive"))
    )
    (net (code "68") (name "unconnected-(U3-PA11{slash}TIM1_CH4{slash}U1_CTS{slash}CAN1_RX{slash}OTG_FS_DM-Pad103)") (class "Default")
      (node (ref "U3") (pin "103") (pinfunction "PA11/TIM1_CH4/U1_CTS/CAN1_RX/OTG_FS_DM_103") (pintype "passive"))
    )
    (net (code "69") (name "unconnected-(U3-PA12{slash}TIM1_ETR{slash}U1_RTS{slash}CAN1_TX{slash}OTG_FS_DP-Pad104)") (class "Default")
      (node (ref "U3") (pin "104") (pinfunction "PA12/TIM1_ETR/U1_RTS/CAN1_TX/OTG_FS_DP_104") (pintype "passive"))
    )
    (net (code "70") (name "unconnected-(U3-PA15{slash}JTDI{slash}SPI1_NSS{slash}SPI3_NSS{slash}TIM2_CH1_ETR{slash}I2S3_WS-Pad110)") (class "Default")
      (node (ref "U3") (pin "110") (pinfunction "PA15/JTDI/SPI1_NSS/SPI3_NSS/TIM2_CH1_ETR/I2S3_WS_110") (pintype "passive"))
    )
    (net (code "71") (name "unconnected-(U3-PB0{slash}TIM1_CH2N{slash}TIM3_CH3{slash}TIM8_CH2N{slash}OTG_HS_ULPI_D1{slash}ETH_MII_RXD2{slash}ADC12_IN8-Pad46)") (class "Default")
      (node (ref "U3") (pin "46") (pinfunction "PB0/TIM1_CH2N/TIM3_CH3/TIM8_CH2N/OTG_HS_ULPI_D1/ETH_MII_RXD2/ADC12_IN8_46") (pintype "passive"))
    )
    (net (code "72") (name "unconnected-(U3-PB1{slash}TIM1_CH3N{slash}TIM3_CH4{slash}TIM8_CH3N{slash}OTG_HS_INTN{slash}ETH_MII_RXD3{slash}ADC12_IN9-Pad47)") (class "Default")
      (node (ref "U3") (pin "47") (pinfunction "PB1/TIM1_CH3N/TIM3_CH4/TIM8_CH3N/OTG_HS_INTN/ETH_MII_RXD3/ADC12_IN9_47") (pintype "passive"))
    )
    (net (code "73") (name "unconnected-(U3-PB3{slash}JTDO{slash}TRACESWO{slash}TIM2_CH2{slash}SPI1_SCK{slash}SPI3_SCK{slash}I2S3_CK-Pad133)") (class "Default")
      (node (ref "U3") (pin "133") (pinfunction "PB3/JTDO/TRACESWO/TIM2_CH2/SPI1_SCK/SPI3_SCK/I2S3_CK_133") (pintype "passive"))
    )
    (net (code "74") (name "unconnected-(U3-PB4{slash}JNTRST{slash}TIM3_CH1{slash}SPI1_MISO{slash}SPI3_MISO{slash}I2S3ext_SD-Pad134)") (class "Default")
      (node (ref "U3") (pin "134") (pinfunction "PB4/JNTRST/TIM3_CH1/SPI1_MISO/SPI3_MISO/I2S3ext_SD_134") (pintype "passive"))
    )
    (net (code "75") (name "unconnected-(U3-PB9{slash}TIM4_CH4{slash}TIM11_CH1{slash}CAN1_TX{slash}SDIO_D5{slash}SPI2_NSS{slash}I2C1_SDA{slash}DCMI_D7{slash}I2S2_WS-Pad140)") (class "Default")
      (node (ref "U3") (pin "140") (pinfunction "PB9/TIM4_CH4/TIM11_CH1/CAN1_TX/SDIO_D5/SPI2_NSS/I2C1_SDA/DCMI_D7/I2S2_WS_140") (pintype "passive"))
    )
    (net (code "76") (name "unconnected-(U3-PC0{slash}OTG_HS_ULPI_STP{slash}ADC123_IN10-Pad26)") (class "Default")
      (node (ref "U3") (pin "26") (pinfunction "PC0/OTG_HS_ULPI_STP/ADC123_IN10_26") (pintype "passive"))
    )
    (net (code "77") (name "unconnected-(U3-PC1{slash}ETH_MDC{slash}ADC123_IN11-Pad27)") (class "Default")
      (node (ref "U3") (pin "27") (pinfunction "PC1/ETH_MDC/ADC123_IN11_27") (pintype "passive"))
    )
    (net (code "78") (name "unconnected-(U3-PC2{slash}SPI2_MISO{slash}OTG_HS_ULPI_DIR{slash}ETH_MII_TXD2{slash}I2S2ext_SD{slash}ADC123_IN12-Pad28)") (class "Default")
      (node (ref "U3") (pin "28") (pinfunction "PC2/SPI2_MISO/OTG_HS_ULPI_DIR/ETH_MII_TXD2/I2S2ext_SD/ADC123_IN12_28") (pintype "passive"))
    )
    (net (code "79") (name "unconnected-(U3-PC3{slash}SPI2_MOSI{slash}OTG_HS_ULPI_NXT{slash}ETH_MII_TX_CLK{slash}I2S2_SD{slash}ADC123_IN13-Pad29)") (class "Default")
      (node (ref "U3") (pin "29") (pinfunction "PC3/SPI2_MOSI/OTG_HS_ULPI_NXT/ETH_MII_TX_CLK/I2S2_SD/ADC123_IN13_29") (pintype "passive"))
    )
    (net (code "80") (name "unconnected-(U3-PC6{slash}TIM3_CH1{slash}TIM8_CH1{slash}U6_TX{slash}SDIO_D6{slash}DCMI_D0{slash}I2S2_MCK-Pad96)") (class "Default")
      (node (ref "U3") (pin "96") (pinfunction "PC6/TIM3_CH1/TIM8_CH1/U6_TX/SDIO_D6/DCMI_D0/I2S2_MCK_96") (pintype "passive"))
    )
    (net (code "81") (name "unconnected-(U3-PC7{slash}TIM3_CH2{slash}TIM8_CH2{slash}U6_RX{slash}SDIO_D7{slash}DCMI_D1{slash}I2S3_MCK-Pad97)") (class "Default")
      (node (ref "U3") (pin "97") (pinfunction "PC7/TIM3_CH2/TIM8_CH2/U6_RX/SDIO_D7/DCMI_D1/I2S3_MCK_97") (pintype "passive"))
    )
    (net (code "82") (name "unconnected-(U3-PC8{slash}TIM3_CH3{slash}TIM8_CH3{slash}U6_CK{slash}SDIO_D0{slash}DCMI_D2-Pad98)") (class "Default")
      (node (ref "U3") (pin "98") (pinfunction "PC8/TIM3_CH3/TIM8_CH3/U6_CK/SDIO_D0/DCMI_D2_98") (pintype "passive"))
    )
    (net (code "83") (name "unconnected-(U3-PC9{slash}TIM3_CH4{slash}TIM8_CH4{slash}I2C3_SDA{slash}SDIO_D1{slash}DCMI_D3{slash}MCO2{slash}I2S_CKIN-Pad99)") (class "Default")
      (node (ref "U3") (pin "99") (pinfunction "PC9/TIM3_CH4/TIM8_CH4/I2C3_SDA/SDIO_D1/DCMI_D3/MCO2/I2S_CKIN_99") (pintype "passive"))
    )
    (net (code "84") (name "unconnected-(U3-PC13{slash}RTC_AF1-Pad7)") (class "Default")
      (node (ref "U3") (pin "7") (pinfunction "PC13/RTC_AF1_7") (pintype "passive"))
    )
    (net (code "85") (name "unconnected-(U3-PD3{slash}FSMC_CLK{slash}U2_CTS-Pad117)") (class "Default")
      (node (ref "U3") (pin "117") (pinfunction "PD3/FSMC_CLK/U2_CTS_117") (pintype "passive"))
    )
    (net (code "86") (name "unconnected-(U3-PD4{slash}FSMC_NOE{slash}U2_RTS-Pad118)") (class "Default")
      (node (ref "U3") (pin "118") (pinfunction "PD4/FSMC_NOE/U2_RTS_118") (pintype "passive"))
    )
    (net (code "87") (name "unconnected-(U3-PD7{slash}FSMC_NE1{slash}FSMC_NCE2{slash}U2_CK-Pad123)") (class "Default")
      (node (ref "U3") (pin "123") (pinfunction "PD7/FSMC_NE1/FSMC_NCE2/U2_CK_123") (pintype "passive"))
    )
    (net (code "88") (name "unconnected-(U3-PD10{slash}FSMC_D15{slash}U3_CK-Pad79)") (class "Default")
      (node (ref "U3") (pin "79") (pinfunction "PD10/FSMC_D15/U3_CK_79") (pintype "passive"))
    )
    (net (code "89") (name "unconnected-(U3-PD11{slash}FSMC_A16{slash}FSMC_CLE{slash}U3_CTS-Pad80)") (class "Default")
      (node (ref "U3") (pin "80") (pinfunction "PD11/FSMC_A16/FSMC_CLE/U3_CTS_80") (pintype "passive"))
    )
    (net (code "90") (name "unconnected-(U3-PD13{slash}FSMC_A18{slash}TIM4_CH2-Pad82)") (class "Default")
      (node (ref "U3") (pin "82") (pinfunction "PD13/FSMC_A18/TIM4_CH2_82") (pintype "passive"))
    )
    (net (code "91") (name "unconnected-(U3-PD14{slash}FSMC_D0{slash}TIM4_CH3-Pad85)") (class "Default")
      (node (ref "U3") (pin "85") (pinfunction "PD14/FSMC_D0/TIM4_CH3_85") (pintype "passive"))
    )
    (net (code "92") (name "unconnected-(U3-PD15{slash}FSMC_D1{slash}TIM4_CH4-Pad86)") (class "Default")
      (node (ref "U3") (pin "86") (pinfunction "PD15/FSMC_D1/TIM4_CH4_86") (pintype "passive"))
    )
    (net (code "93") (name "unconnected-(U3-PE0{slash}TIM4_ETR{slash}FSMC_NBL0{slash}DCMI_D2-Pad141)") (class "Default")
      (node (ref "U3") (pin "141") (pinfunction "PE0/TIM4_ETR/FSMC_NBL0/DCMI_D2_141") (pintype "passive"))
    )
    (net (code "94") (name "unconnected-(U3-PE1{slash}FSMC_NBL1{slash}DCMI_D3-Pad142)") (class "Default")
      (node (ref "U3") (pin "142") (pinfunction "PE1/FSMC_NBL1/DCMI_D3_142") (pintype "passive"))
    )
    (net (code "95") (name "unconnected-(U3-PE2{slash}TRACECLK{slash}FSMC_A23{slash}ETH_MII_TXD3-Pad1)") (class "Default")
      (node (ref "U3") (pin "1") (pinfunction "PE2/TRACECLK/FSMC_A23/ETH_MII_TXD3_1") (pintype "passive"))
    )
    (net (code "96") (name "unconnected-(U3-PE3{slash}TRACED0{slash}FSMC_A19-Pad2)") (class "Default")
      (node (ref "U3") (pin "2") (pinfunction "PE3/TRACED0/FSMC_A19_2") (pintype "passive"))
    )
    (net (code "97") (name "unconnected-(U3-PE4{slash}TRACED1{slash}FSMC_A20{slash}DCMI_D4-Pad3)") (class "Default")
      (node (ref "U3") (pin "3") (pinfunction "PE4/TRACED1/FSMC_A20/DCMI_D4_3") (pintype "passive"))
    )
    (net (code "98") (name "unconnected-(U3-PE5{slash}TRACED2{slash}FSMC_A21{slash}TIM9_CH1{slash}DCMI_D6-Pad4)") (class "Default")
      (node (ref "U3") (pin "4") (pinfunction "PE5/TRACED2/FSMC_A21/TIM9_CH1/DCMI_D6_4") (pintype "passive"))
    )
    (net (code "99") (name "unconnected-(U3-PE6{slash}TRACED3{slash}FSMC_A22{slash}TIM9_CH2{slash}DCMI_D7-Pad5)") (class "Default")
      (node (ref "U3") (pin "5") (pinfunction "PE6/TRACED3/FSMC_A22/TIM9_CH2/DCMI_D7_5") (pintype "passive"))
    )
    (net (code "100") (name "unconnected-(U3-PE7{slash}FSMC_D4{slash}TIM1_ETR-Pad58)") (class "Default")
      (node (ref "U3") (pin "58") (pinfunction "PE7/FSMC_D4/TIM1_ETR_58") (pintype "passive"))
    )
    (net (code "101") (name "unconnected-(U3-PE8{slash}FSMC_D5{slash}TIM1_CH1N-Pad59)") (class "Default")
      (node (ref "U3") (pin "59") (pinfunction "PE8/FSMC_D5/TIM1_CH1N_59") (pintype "passive"))
    )
    (net (code "102") (name "unconnected-(U3-PE9{slash}FSMC_D6{slash}TIM1_CH1-Pad60)") (class "Default")
      (node (ref "U3") (pin "60") (pinfunction "PE9/FSMC_D6/TIM1_CH1_60") (pintype "passive"))
    )
    (net (code "103") (name "unconnected-(U3-PE10{slash}FSMC_D7{slash}TIM1_CH2N-Pad63)") (class "Default")
      (node (ref "U3") (pin "63") (pinfunction "PE10/FSMC_D7/TIM1_CH2N_63") (pintype "passive"))
    )
    (net (code "104") (name "unconnected-(U3-PE11{slash}FSMC_D8{slash}TIM1_CH2-Pad64)") (class "Default")
      (node (ref "U3") (pin "64") (pinfunction "PE11/FSMC_D8/TIM1_CH2_64") (pintype "passive"))
    )
    (net (code "105") (name "unconnected-(U3-PE12{slash}FSMC_D9{slash}TIM1_CH3N-Pad65)") (class "Default")
      (node (ref "U3") (pin "65") (pinfunction "PE12/FSMC_D9/TIM1_CH3N_65") (pintype "passive"))
    )
    (net (code "106") (name "unconnected-(U3-PE13{slash}FSMC_D10{slash}TIM1_CH3-Pad66)") (class "Default")
      (node (ref "U3") (pin "66") (pinfunction "PE13/FSMC_D10/TIM1_CH3_66") (pintype "passive"))
    )
    (net (code "107") (name "unconnected-(U3-PE14{slash}FSMC_D11{slash}TIM1_CH4-Pad67)") (class "Default")
      (node (ref "U3") (pin "67") (pinfunction "PE14/FSMC_D11/TIM1_CH4_67") (pintype "passive"))
    )
    (net (code "108") (name "unconnected-(U3-PE15{slash}FSMC_D12{slash}TIM1_BKIN-Pad68)") (class "Default")
      (node (ref "U3") (pin "68") (pinfunction "PE15/FSMC_D12/TIM1_BKIN_68") (pintype "passive"))
    )
    (net (code "109") (name "unconnected-(U3-PF2{slash}FSMC_A2{slash}I2C2_SMBA-Pad12)") (class "Default")
      (node (ref "U3") (pin "12") (pinfunction "PF2/FSMC_A2/I2C2_SMBA_12") (pintype "passive"))
    )
    (net (code "110") (name "unconnected-(U3-PF3{slash}FSMC_A3{slash}ADC3_IN9-Pad13)") (class "Default")
      (node (ref "U3") (pin "13") (pinfunction "PF3/FSMC_A3/ADC3_IN9_13") (pintype "passive"))
    )
    (net (code "111") (name "unconnected-(U3-PF4{slash}FSMC_A4{slash}ADC3_IN14-Pad14)") (class "Default")
      (node (ref "U3") (pin "14") (pinfunction "PF4/FSMC_A4/ADC3_IN14_14") (pintype "passive"))
    )
    (net (code "112") (name "unconnected-(U3-PF5{slash}FSMC_A5{slash}ADC3_IN15-Pad15)") (class "Default")
      (node (ref "U3") (pin "15") (pinfunction "PF5/FSMC_A5/ADC3_IN15_15") (pintype "passive"))
    )
    (net (code "113") (name "unconnected-(U3-PF6{slash}TIM10_CH1{slash}FSMC_NIORD{slash}ADC3_IN4-Pad18)") (class "Default")
      (node (ref "U3") (pin "18") (pinfunction "PF6/TIM10_CH1/FSMC_NIORD/ADC3_IN4_18") (pintype "passive"))
    )
    (net (code "114") (name "unconnected-(U3-PF7{slash}TIM11_CH1{slash}FSMC_NREG{slash}ADC3_IN5-Pad19)") (class "Default")
      (node (ref "U3") (pin "19") (pinfunction "PF7/TIM11_CH1/FSMC_NREG/ADC3_IN5_19") (pintype "passive"))
    )
    (net (code "115") (name "unconnected-(U3-PF8{slash}TIM13_CH1{slash}FSMC_NIOWR{slash}ADC3_IN6-Pad20)") (class "Default")
      (node (ref "U3") (pin "20") (pinfunction "PF8/TIM13_CH1/FSMC_NIOWR/ADC3_IN6_20") (pintype "passive"))
    )
    (net (code "116") (name "unconnected-(U3-PF9{slash}TIM14_CH1{slash}FSMC_CD{slash}ADC3_IN7-Pad21)") (class "Default")
      (node (ref "U3") (pin "21") (pinfunction "PF9/TIM14_CH1/FSMC_CD/ADC3_IN7_21") (pintype "passive"))
    )
    (net (code "117") (name "unconnected-(U3-PF10{slash}FSMC_INTR{slash}ADC3_IN8-Pad22)") (class "Default")
      (node (ref "U3") (pin "22") (pinfunction "PF10/FSMC_INTR/ADC3_IN8_22") (pintype "passive"))
    )
    (net (code "118") (name "unconnected-(U3-PF11{slash}DCMI_D12-Pad49)") (class "Default")
      (node (ref "U3") (pin "49") (pinfunction "PF11/DCMI_D12_49") (pintype "passive"))
    )
    (net (code "119") (name "unconnected-(U3-PF12{slash}FSMC_A6-Pad50)") (class "Default")
      (node (ref "U3") (pin "50") (pinfunction "PF12/FSMC_A6_50") (pintype "passive"))
    )
    (net (code "120") (name "unconnected-(U3-PF13{slash}FSMC_A7-Pad53)") (class "Default")
      (node (ref "U3") (pin "53") (pinfunction "PF13/FSMC_A7_53") (pintype "passive"))
    )
    (net (code "121") (name "unconnected-(U3-PF14{slash}FSMC_A8-Pad54)") (class "Default")
      (node (ref "U3") (pin "54") (pinfunction "PF14/FSMC_A8_54") (pintype "passive"))
    )
    (net (code "122") (name "unconnected-(U3-PF15{slash}FSMC_A9-Pad55)") (class "Default")
      (node (ref "U3") (pin "55") (pinfunction "PF15/FSMC_A9_55") (pintype "passive"))
    )
    (net (code "123") (name "unconnected-(U3-PG0{slash}FSMC_A10-Pad56)") (class "Default")
      (node (ref "U3") (pin "56") (pinfunction "PG0/FSMC_A10_56") (pintype "passive"))
    )
    (net (code "124") (name "unconnected-(U3-PG1{slash}FSMC_A11-Pad57)") (class "Default")
      (node (ref "U3") (pin "57") (pinfunction "PG1/FSMC_A11_57") (pintype "passive"))
    )
    (net (code "125") (name "unconnected-(U3-PG2{slash}FSMC_A12-Pad87)") (class "Default")
      (node (ref "U3") (pin "87") (pinfunction "PG2/FSMC_A12_87") (pintype "passive"))
    )
    (net (code "126") (name "unconnected-(U3-PG3{slash}FSMC_A13-Pad88)") (class "Default")
      (node (ref "U3") (pin "88") (pinfunction "PG3/FSMC_A13_88") (pintype "passive"))
    )
    (net (code "127") (name "unconnected-(U3-PG4{slash}FSMC_A14-Pad89)") (class "Default")
      (node (ref "U3") (pin "89") (pinfunction "PG4/FSMC_A14_89") (pintype "passive"))
    )
    (net (code "128") (name "unconnected-(U3-PG5{slash}FSMC_A15-Pad90)") (class "Default")
      (node (ref "U3") (pin "90") (pinfunction "PG5/FSMC_A15_90") (pintype "passive"))
    )
    (net (code "129") (name "unconnected-(U3-PG6{slash}FSMC_INT2-Pad91)") (class "Default")
      (node (ref "U3") (pin "91") (pinfunction "PG6/FSMC_INT2_91") (pintype "passive"))
    )
    (net (code "130") (name "unconnected-(U3-PG7{slash}FSMC_INT3{slash}U6_CK-Pad92)") (class "Default")
      (node (ref "U3") (pin "92") (pinfunction "PG7/FSMC_INT3/U6_CK_92") (pintype "passive"))
    )
    (net (code "131") (name "unconnected-(U3-PG8{slash}U6_RTS{slash}ETH_PPS_OUT-Pad93)") (class "Default")
      (node (ref "U3") (pin "93") (pinfunction "PG8/U6_RTS/ETH_PPS_OUT_93") (pintype "passive"))
    )
    (net (code "132") (name "unconnected-(U3-PG10{slash}FSMC_NCE4_1{slash}FSMC_NE3-Pad125)") (class "Default")
      (node (ref "U3") (pin "125") (pinfunction "PG10/FSMC_NCE4_1/FSMC_NE3_125") (pintype "passive"))
    )
    (net (code "133") (name "unconnected-(U3-PG11{slash}FSMC_NCE4_2{slash}ETH_MII_TX_EN{slash}ETH_RMII_TX_EN-Pad126)") (class "Default")
      (node (ref "U3") (pin "126") (pinfunction "PG11/FSMC_NCE4_2/ETH_MII_TX_EN/ETH_RMII_TX_EN_126") (pintype "passive"))
    )
    (net (code "134") (name "unconnected-(U3-PG13{slash}FSMC_A24{slash}U6_CTS{slash}ETH_MII_TXD0{slash}ETH_RMII_TXD0-Pad128)") (class "Default")
      (node (ref "U3") (pin "128") (pinfunction "PG13/FSMC_A24/U6_CTS/ETH_MII_TXD0/ETH_RMII_TXD0_128") (pintype "passive"))
    )
    (net (code "135") (name "unconnected-(U3-PG15{slash}U6_CTS{slash}DCMI_D13-Pad132)") (class "Default")
      (node (ref "U3") (pin "132") (pinfunction "PG15/U6_CTS/DCMI_D13_132") (pintype "passive"))
    )
    (net (code "136") (name "unconnected-(U4-AUX_CL-Pad7)") (class "Default")
      (node (ref "U4") (pin "7") (pinfunction "AUX_CL_7") (pintype "passive+no_connect"))
    )
    (net (code "137") (name "unconnected-(U4-AUX_DA-Pad21)") (class "Default")
      (node (ref "U4") (pin "21") (pinfunction "AUX_DA_21") (pintype "passive+no_connect"))
    )
    (net (code "138") (name "unconnected-(U4-NC-Pad1)") (class "Default")
      (node (ref "U4") (pin "1") (pinfunction "NC_1") (pintype "passive+no_connect"))
    )
    (net (code "139") (name "unconnected-(U4-NC-Pad2)") (class "Default")
      (node (ref "U4") (pin "2") (pinfunction "NC_2") (pintype "passive+no_connect"))
    )
    (net (code "140") (name "unconnected-(U4-NC-Pad3)") (class "Default")
      (node (ref "U4") (pin "3") (pinfunction "NC_3") (pintype "passive+no_connect"))
    )
    (net (code "141") (name "unconnected-(U4-NC-Pad4)") (class "Default")
      (node (ref "U4") (pin "4") (pinfunction "NC_4") (pintype "passive+no_connect"))
    )
    (net (code "142") (name "unconnected-(U4-NC-Pad5)") (class "Default")
      (node (ref "U4") (pin "5") (pinfunction "NC_5") (pintype "passive+no_connect"))
    )
    (net (code "143") (name "unconnected-(U4-NC-Pad6)") (class "Default")
      (node (ref "U4") (pin "6") (pinfunction "NC_6") (pintype "passive+no_connect"))
    )
    (net (code "144") (name "unconnected-(U4-NC-Pad14)") (class "Default")
      (node (ref "U4") (pin "14") (pinfunction "NC_14") (pintype "passive+no_connect"))
    )
    (net (code "145") (name "unconnected-(U4-NC-Pad15)") (class "Default")
      (node (ref "U4") (pin "15") (pinfunction "NC_15") (pintype "passive+no_connect"))
    )
    (net (code "146") (name "unconnected-(U4-NC-Pad16)") (class "Default")
      (node (ref "U4") (pin "16") (pinfunction "NC_16") (pintype "passive+no_connect"))
    )
    (net (code "147") (name "unconnected-(U4-NC-Pad17)") (class "Default")
      (node (ref "U4") (pin "17") (pinfunction "NC_17") (pintype "passive+no_connect"))
    )
    (net (code "148") (name "unconnected-(U4-RESV-Pad19)") (class "Default")
      (node (ref "U4") (pin "19") (pinfunction "RESV_19") (pintype "passive+no_connect"))
    )
    (net (code "149") (name "unconnected-(U5-NC-Pad1)") (class "Default")
      (node (ref "U5") (pin "1") (pinfunction "NC_1") (pintype "passive+no_connect"))
    )
    (net (code "150") (name "unconnected-(U6-NC-Pad1)") (class "Default")
      (node (ref "U6") (pin "1") (pinfunction "NC_1") (pintype "passive+no_connect"))
    )
  )
)
